# motor_driver_2.net
KiCad netlist of a schematic drawn in Altium Designer
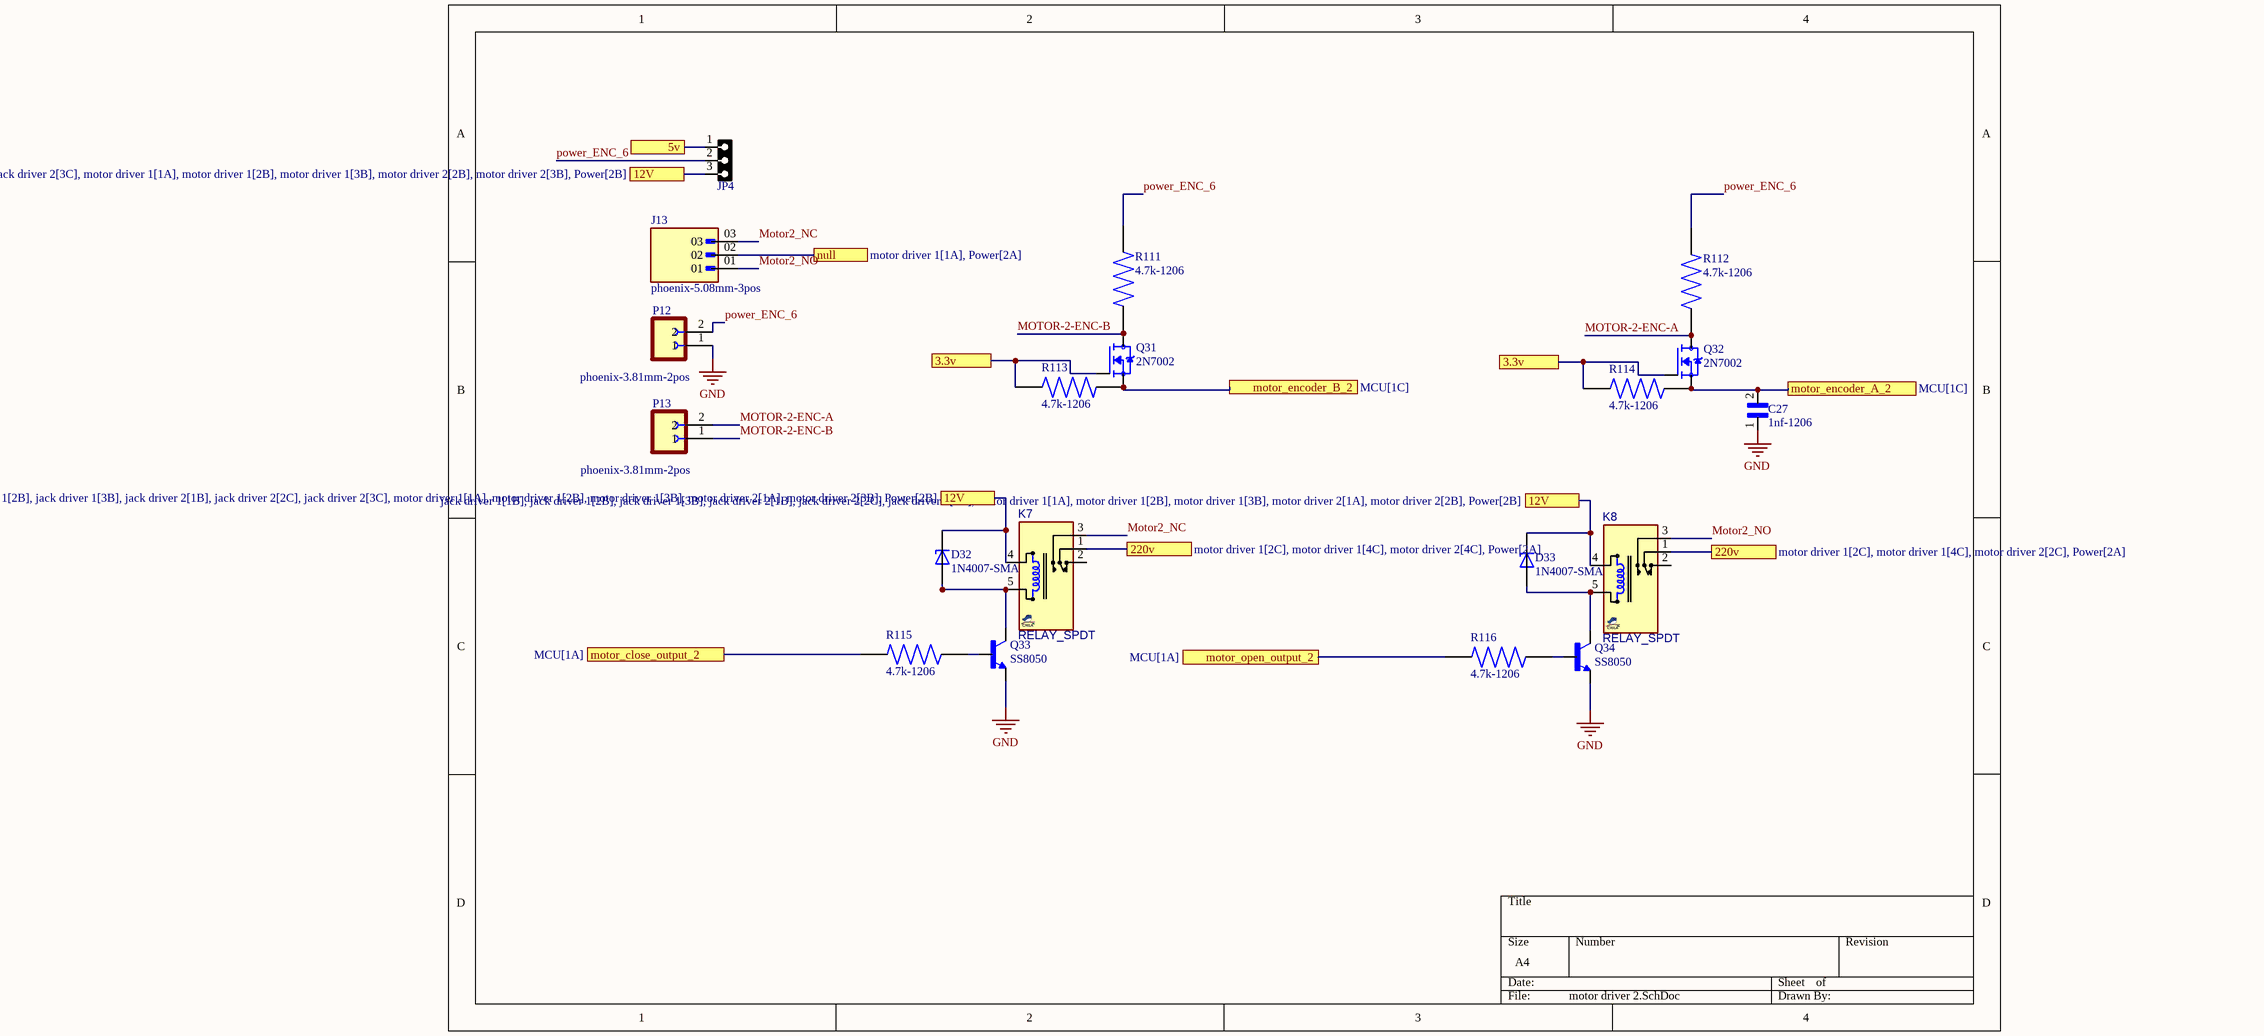
[diagram p0: motor driver 2.SchDoc]

(export (version "E")
  (design (tool "Eeschema 10.0.6"))
  (components
    (comp (ref "C27")
      (value "1nf-1206")
      (footprint "CAPC3216X180N")
      (description "1ÂµF Â±20% 50V Ceramic Capacitor X8R 1206 (3216 Metric)")
      (fields (field (name "MF") "TDK") (field (name "MP") "CGA5L3X8R1H105M160AB"))
      (libsource (lib "cap-1206") (part "CGA5L3X8R1H105M160AB"))
    )
    (comp (ref "D32")
      (value "1N4007-SMA")
      (footprint "DIOM4325X250N")
      (description "400W, 30.4V, 5%, Unidirectional, TVS")
      (fields (field (name "MF") "Taiwan Semiconductor") (field (name "MP") "SMAJ26A"))
      (libsource (lib "diode-sma") (part "SMAJ26A"))
    )
    (comp (ref "D33")
      (value "1N4007-SMA")
      (footprint "DIOM4325X250N")
      (description "400W, 30.4V, 5%, Unidirectional, TVS")
      (fields (field (name "MF") "Taiwan Semiconductor") (field (name "MP") "SMAJ26A"))
      (libsource (lib "diode-sma") (part "SMAJ26A"))
    )
    (comp (ref "J13")
      (value "phoenix-5.08mm-3pos")
      (footprint "PHOENIX_1759020")
      (description "Pluggable Header 5.08mm 12AWG 320V 12A 3 Position COMBICON MSTB Series ¦ Phoenix Contact 1759020")
      (fields (field (name "MF") "Phoenix Contact") (field (name "MP") "1759020"))
      (libsource (lib "phoenix-3pos") (part "1759020"))
    )
    (comp (ref "JP4")
      (value "HDRF3")
      (footprint "HDRLP_F_1X3")
      (description "CONN, HEADER, Male, pitch: 2.54mm, 3POS")
      (libsource (lib "conn_2.54mm_lp") (part "HDRLP_F_1X3"))
    )
    (comp (ref "K7")
      (value "RELAY_SPDT")
      (footprint "REL_SPDT_5_1512")
      (description "Relay, SPDT, 5P, 15.4X12.1mm, 16V/30A")
      (fields (field (name "MANF") "OMRON") (field (name "MANF_P#") "G8QN-1C4 DC12"))
      (libsource (lib "relay") (part "RELAY_SPDT_5_1512_G8QN"))
    )
    (comp (ref "K8")
      (value "RELAY_SPDT")
      (footprint "REL_SPDT_5_1512")
      (description "Relay, SPDT, 5P, 15.4X12.1mm, 16V/30A")
      (fields (field (name "MANF") "OMRON") (field (name "MANF_P#") "G8QN-1C4 DC12"))
      (libsource (lib "relay") (part "RELAY_SPDT_5_1512_G8QN"))
    )
    (comp (ref "P12")
      (value "phoenix-3.81mm-2pos")
      (footprint "PHOENIX_1803578")
      (description "2 Position Terminal Block Plug, Female Sockets 0.150 (3.81mm) 180Â° Free Hanging (In-Line)")
      (fields (field (name "MF") "Phoenix Contact") (field (name "MP") "1803578"))
      (libsource (lib "terminal-phoenix-3.81mm-2pos") (part "1803578"))
    )
    (comp (ref "P13")
      (value "phoenix-3.81mm-2pos")
      (footprint "PHOENIX_1803578")
      (description "2 Position Terminal Block Plug, Female Sockets 0.150 (3.81mm) 180Â° Free Hanging (In-Line)")
      (fields (field (name "MF") "Phoenix Contact") (field (name "MP") "1803578"))
      (libsource (lib "terminal-phoenix-3.81mm-2pos") (part "1803578"))
    )
    (comp (ref "Q31")
      (value "2N7002")
      (footprint "SOT95P240X111-3N")
      (description "N-Channel 60V 280mA (Ta) 350mW (Ta) Surface Mount SOT-23-3 (TO-236)")
      (fields (field (name "MF") "{'manufacturer': u'onsemi'}"))
      (libsource (lib "2N7002-SOT23") (part "2N7002"))
    )
    (comp (ref "Q32")
      (value "2N7002")
      (footprint "SOT95P240X111-3N")
      (description "N-Channel 60V 280mA (Ta) 350mW (Ta) Surface Mount SOT-23-3 (TO-236)")
      (fields (field (name "MF") "{'manufacturer': u'onsemi'}"))
      (libsource (lib "2N7002-SOT23") (part "2N7002"))
    )
    (comp (ref "Q33")
      (value "SS8050")
      (footprint "TRANS_SS8050-G")
      (description "Bipolar (BJT) Transistor NPN 25 V 1.5 A 100MHz 300 mW Surface Mount SOT-23-3")
      (fields (field (name "DIGI-KEY_PART_NUMBER") "641-1790-2-ND") (field (name "MP") "SS8050G"))
      (libsource (lib "SS8050-G") (part "SS8050-G"))
    )
    (comp (ref "Q34")
      (value "SS8050")
      (footprint "TRANS_SS8050-G")
      (description "Bipolar (BJT) Transistor NPN 25 V 1.5 A 100MHz 300 mW Surface Mount SOT-23-3")
      (fields (field (name "DIGI-KEY_PART_NUMBER") "641-1790-2-ND") (field (name "MP") "SS8050G"))
      (libsource (lib "SS8050-G") (part "SS8050-G"))
    )
    (comp (ref "R111")
      (value "4.7k-1206")
      (footprint "RESC3015X65N")
      (description "Res Thin Film 1206 10K Ohm 0.1% 1/8W Â±25ppm/Â°C Molded SMD SMD Paper T/R")
      (fields (field (name "MF") "TE Connectivity") (field (name "MP") "CPF1206B10KE1"))
      (libsource (lib "resistor-1206") (part "CPF1206B10KE1"))
    )
    (comp (ref "R112")
      (value "4.7k-1206")
      (footprint "RESC3015X65N")
      (description "Res Thin Film 1206 10K Ohm 0.1% 1/8W Â±25ppm/Â°C Molded SMD SMD Paper T/R")
      (fields (field (name "MF") "TE Connectivity") (field (name "MP") "CPF1206B10KE1"))
      (libsource (lib "resistor-1206") (part "CPF1206B10KE1"))
    )
    (comp (ref "R113")
      (value "4.7k-1206")
      (footprint "RESC3015X65N")
      (description "Res Thin Film 1206 10K Ohm 0.1% 1/8W Â±25ppm/Â°C Molded SMD SMD Paper T/R")
      (fields (field (name "MF") "TE Connectivity") (field (name "MP") "CPF1206B10KE1"))
      (libsource (lib "resistor-1206") (part "CPF1206B10KE1"))
    )
    (comp (ref "R114")
      (value "4.7k-1206")
      (footprint "RESC3015X65N")
      (description "Res Thin Film 1206 10K Ohm 0.1% 1/8W Â±25ppm/Â°C Molded SMD SMD Paper T/R")
      (fields (field (name "MF") "TE Connectivity") (field (name "MP") "CPF1206B10KE1"))
      (libsource (lib "resistor-1206") (part "CPF1206B10KE1"))
    )
    (comp (ref "R115")
      (value "4.7k-1206")
      (footprint "RESC3015X65N")
      (description "Res Thin Film 1206 10K Ohm 0.1% 1/8W Â±25ppm/Â°C Molded SMD SMD Paper T/R")
      (fields (field (name "MF") "TE Connectivity") (field (name "MP") "CPF1206B10KE1"))
      (libsource (lib "resistor-1206") (part "CPF1206B10KE1"))
    )
    (comp (ref "R116")
      (value "4.7k-1206")
      (footprint "RESC3015X65N")
      (description "Res Thin Film 1206 10K Ohm 0.1% 1/8W Â±25ppm/Â°C Molded SMD SMD Paper T/R")
      (fields (field (name "MF") "TE Connectivity") (field (name "MP") "CPF1206B10KE1"))
      (libsource (lib "resistor-1206") (part "CPF1206B10KE1"))
    )
  )
  (nets
    (net (code "1") (name "/3.3v") (class "Default")
      (node (ref "Q31") (pin "1") (pinfunction "G_1") (pintype "passive"))
      (node (ref "Q32") (pin "1") (pinfunction "G_1") (pintype "passive"))
      (node (ref "R113") (pin "2") (pinfunction "2_2") (pintype "passive"))
      (node (ref "R114") (pin "2") (pinfunction "2_2") (pintype "passive"))
    )
    (net (code "2") (name "/5v") (class "Default")
      (node (ref "JP4") (pin "1") (pinfunction "1_1") (pintype "passive"))
    )
    (net (code "3") (name "/12V") (class "Default")
      (node (ref "D32") (pin "C") (pinfunction "C_C") (pintype "passive"))
      (node (ref "D33") (pin "C") (pinfunction "C_C") (pintype "passive"))
      (node (ref "JP4") (pin "3") (pinfunction "3_3") (pintype "passive"))
      (node (ref "K7") (pin "4") (pinfunction "T1_4") (pintype "passive"))
      (node (ref "K8") (pin "4") (pinfunction "T1_4") (pintype "passive"))
    )
    (net (code "4") (name "/220v") (class "Default")
      (node (ref "K7") (pin "1") (pinfunction "COM_1") (pintype "passive"))
      (node (ref "K8") (pin "1") (pinfunction "COM_1") (pintype "passive"))
    )
    (net (code "5") (name "/MOTOR-2-ENC-A") (class "Default")
      (node (ref "P13") (pin "2") (pinfunction "2_2") (pintype "passive"))
      (node (ref "Q32") (pin "3") (pinfunction "D_3") (pintype "passive"))
      (node (ref "R112") (pin "1") (pinfunction "1_1") (pintype "passive"))
    )
    (net (code "6") (name "/MOTOR-2-ENC-B") (class "Default")
      (node (ref "P13") (pin "1") (pinfunction "1_1") (pintype "passive"))
      (node (ref "Q31") (pin "3") (pinfunction "D_3") (pintype "passive"))
      (node (ref "R111") (pin "1") (pinfunction "1_1") (pintype "passive"))
    )
    (net (code "7") (name "/Motor2_NC") (class "Default")
      (node (ref "J13") (pin "03") (pinfunction "03_03") (pintype "passive"))
      (node (ref "K7") (pin "3") (pinfunction "NO_3") (pintype "passive"))
    )
    (net (code "8") (name "/Motor2_NO") (class "Default")
      (node (ref "J13") (pin "01") (pinfunction "01_01") (pintype "passive"))
      (node (ref "K8") (pin "3") (pinfunction "NO_3") (pintype "passive"))
    )
    (net (code "9") (name "/motor_close_output_2") (class "Default")
      (node (ref "R115") (pin "2") (pinfunction "2_2") (pintype "passive"))
    )
    (net (code "10") (name "/motor_encoder_A_2") (class "Default")
      (node (ref "C27") (pin "2") (pinfunction "2_2") (pintype "passive"))
      (node (ref "Q32") (pin "2") (pinfunction "S_2") (pintype "passive"))
      (node (ref "R114") (pin "1") (pinfunction "1_1") (pintype "passive"))
    )
    (net (code "11") (name "/motor_encoder_B_2") (class "Default")
      (node (ref "Q31") (pin "2") (pinfunction "S_2") (pintype "passive"))
      (node (ref "R113") (pin "1") (pinfunction "1_1") (pintype "passive"))
    )
    (net (code "12") (name "/motor_open_output_2") (class "Default")
      (node (ref "R116") (pin "2") (pinfunction "2_2") (pintype "passive"))
    )
    (net (code "13") (name "/null") (class "Default")
      (node (ref "J13") (pin "02") (pinfunction "02_02") (pintype "passive"))
    )
    (net (code "14") (name "/power_ENC_6") (class "Default")
      (node (ref "JP4") (pin "2") (pinfunction "2_2") (pintype "passive"))
      (node (ref "P12") (pin "2") (pinfunction "2_2") (pintype "passive"))
      (node (ref "R111") (pin "2") (pinfunction "2_2") (pintype "passive"))
      (node (ref "R112") (pin "2") (pinfunction "2_2") (pintype "passive"))
    )
    (net (code "15") (name "GND") (class "Default")
      (node (ref "C27") (pin "1") (pinfunction "1_1") (pintype "passive"))
      (node (ref "P12") (pin "1") (pinfunction "1_1") (pintype "passive"))
      (node (ref "Q33") (pin "2") (pinfunction "E_2") (pintype "passive"))
      (node (ref "Q34") (pin "2") (pinfunction "E_2") (pintype "passive"))
    )
    (net (code "16") (name "Net-(K7-T2)") (class "Default")
      (node (ref "D32") (pin "A") (pinfunction "A_A") (pintype "passive"))
      (node (ref "K7") (pin "5") (pinfunction "T2_5") (pintype "passive"))
      (node (ref "Q33") (pin "3") (pinfunction "C_3") (pintype "passive"))
    )
    (net (code "17") (name "Net-(K8-T2)") (class "Default")
      (node (ref "D33") (pin "A") (pinfunction "A_A") (pintype "passive"))
      (node (ref "K8") (pin "5") (pinfunction "T2_5") (pintype "passive"))
      (node (ref "Q34") (pin "3") (pinfunction "C_3") (pintype "passive"))
    )
    (net (code "18") (name "Net-(Q33-B)") (class "Default")
      (node (ref "Q33") (pin "1") (pinfunction "B_1") (pintype "passive"))
      (node (ref "R115") (pin "1") (pinfunction "1_1") (pintype "passive"))
    )
    (net (code "19") (name "Net-(Q34-B)") (class "Default")
      (node (ref "Q34") (pin "1") (pinfunction "B_1") (pintype "passive"))
      (node (ref "R116") (pin "1") (pinfunction "1_1") (pintype "passive"))
    )
    (net (code "20") (name "unconnected-(K7-NC-Pad2)") (class "Default")
      (node (ref "K7") (pin "2") (pinfunction "NC_2") (pintype "passive"))
    )
    (net (code "21") (name "unconnected-(K8-NC-Pad2)") (class "Default")
      (node (ref "K8") (pin "2") (pinfunction "NC_2") (pintype "passive"))
    )
  )
)
